# Digital.net
KiCad netlist of a schematic drawn in Altium Designer
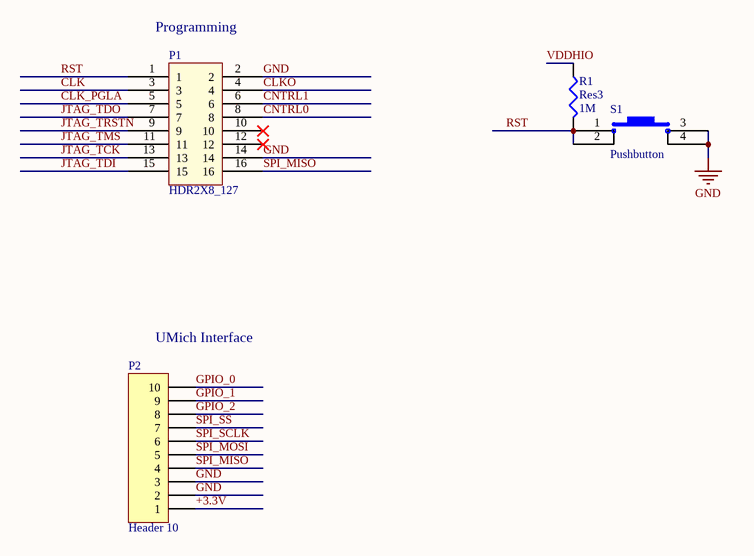
[diagram p0: Digital.SchDoc]

(export (version "E")
  (design (tool "Eeschema 10.0.6"))
  (components
    (comp (ref "P1")
      (value "HDR2X8_127")
      (footprint "HDR2X8_127")
      (description "Header 16 positions 1.27mm")
      (libsource (lib "INERTIA") (part "HDR2X8_127"))
    )
    (comp (ref "P2")
      (value "Header 10")
      (footprint "505110-1092")
      (description "Header, 10-Pin")
      (fields (field (name "PUBLISHER") "Altium Limited"))
      (libsource (lib "Miscellaneous Connectors") (part "Header 10"))
    )
    (comp (ref "R1")
      (value "Res3")
      (footprint "0402")
      (description "Resistor")
      (fields (field (name "ALTIUM_VALUE") "1M") (field (name "PUBLISHER") "Altium Limited"))
      (libsource (lib "Miscellaneous Devices") (part "Res3"))
    )
    (comp (ref "S1")
      (value "Pushbutton")
      (footprint "KMT031")
      (description "Pushbutton, 4 leads")
      (libsource (lib "ASSIST") (part "PB_SW"))
    )
  )
  (nets
    (net (code "1") (name "/+3.3V") (class "Default")
      (node (ref "P2") (pin "1") (pinfunction "1_1") (pintype "passive"))
    )
    (net (code "2") (name "/CLK") (class "Default")
      (node (ref "P1") (pin "3") (pinfunction "3_3") (pintype "passive"))
    )
    (net (code "3") (name "/CLKO") (class "Default")
      (node (ref "P1") (pin "4") (pinfunction "4_4") (pintype "passive"))
    )
    (net (code "4") (name "/CLK_PGLA") (class "Default")
      (node (ref "P1") (pin "5") (pinfunction "5_5") (pintype "passive"))
    )
    (net (code "5") (name "/CNTRL0") (class "Default")
      (node (ref "P1") (pin "8") (pinfunction "8_8") (pintype "passive"))
    )
    (net (code "6") (name "/CNTRL1") (class "Default")
      (node (ref "P1") (pin "6") (pinfunction "6_6") (pintype "passive"))
    )
    (net (code "7") (name "/GPIO_0") (class "Default")
      (node (ref "P2") (pin "10") (pinfunction "10_10") (pintype "passive"))
    )
    (net (code "8") (name "/GPIO_1") (class "Default")
      (node (ref "P2") (pin "9") (pinfunction "9_9") (pintype "passive"))
    )
    (net (code "9") (name "/GPIO_2") (class "Default")
      (node (ref "P2") (pin "8") (pinfunction "8_8") (pintype "passive"))
    )
    (net (code "10") (name "/JTAG_TCK") (class "Default")
      (node (ref "P1") (pin "13") (pinfunction "13_13") (pintype "passive"))
    )
    (net (code "11") (name "/JTAG_TDI") (class "Default")
      (node (ref "P1") (pin "15") (pinfunction "15_15") (pintype "passive"))
    )
    (net (code "12") (name "/JTAG_TDO") (class "Default")
      (node (ref "P1") (pin "7") (pinfunction "7_7") (pintype "passive"))
    )
    (net (code "13") (name "/JTAG_TMS") (class "Default")
      (node (ref "P1") (pin "11") (pinfunction "11_11") (pintype "passive"))
    )
    (net (code "14") (name "/JTAG_TRSTN") (class "Default")
      (node (ref "P1") (pin "9") (pinfunction "9_9") (pintype "passive"))
    )
    (net (code "15") (name "/RST") (class "Default")
      (node (ref "P1") (pin "1") (pinfunction "1_1") (pintype "passive"))
      (node (ref "R1") (pin "2") (pinfunction "2_2") (pintype "passive"))
      (node (ref "S1") (pin "1") (pinfunction "1_1") (pintype "passive"))
      (node (ref "S1") (pin "2") (pinfunction "2_2") (pintype "passive"))
    )
    (net (code "16") (name "/SPI_MISO") (class "Default")
      (node (ref "P1") (pin "16") (pinfunction "16_16") (pintype "passive"))
      (node (ref "P2") (pin "4") (pinfunction "4_4") (pintype "passive"))
    )
    (net (code "17") (name "/SPI_MOSI") (class "Default")
      (node (ref "P2") (pin "5") (pinfunction "5_5") (pintype "passive"))
    )
    (net (code "18") (name "/SPI_SCLK") (class "Default")
      (node (ref "P2") (pin "6") (pinfunction "6_6") (pintype "passive"))
    )
    (net (code "19") (name "/SPI_SS") (class "Default")
      (node (ref "P2") (pin "7") (pinfunction "7_7") (pintype "passive"))
    )
    (net (code "20") (name "/VDDHIO") (class "Default")
      (node (ref "R1") (pin "1") (pinfunction "1_1") (pintype "passive"))
    )
    (net (code "21") (name "GND") (class "Default")
      (node (ref "P1") (pin "14") (pinfunction "14_14") (pintype "passive"))
      (node (ref "P1") (pin "2") (pinfunction "2_2") (pintype "passive"))
      (node (ref "P2") (pin "2") (pinfunction "2_2") (pintype "passive"))
      (node (ref "P2") (pin "3") (pinfunction "3_3") (pintype "passive"))
      (node (ref "S1") (pin "3") (pinfunction "3_3") (pintype "passive"))
      (node (ref "S1") (pin "4") (pinfunction "4_4") (pintype "passive"))
    )
    (net (code "22") (name "unconnected-(P1-Pad10)") (class "Default")
      (node (ref "P1") (pin "10") (pinfunction "10_10") (pintype "passive+no_connect"))
    )
    (net (code "23") (name "unconnected-(P1-Pad12)") (class "Default")
      (node (ref "P1") (pin "12") (pinfunction "12_12") (pintype "passive+no_connect"))
    )
  )
)
